# ADC.net
KiCad netlist of a schematic drawn in Altium Designer
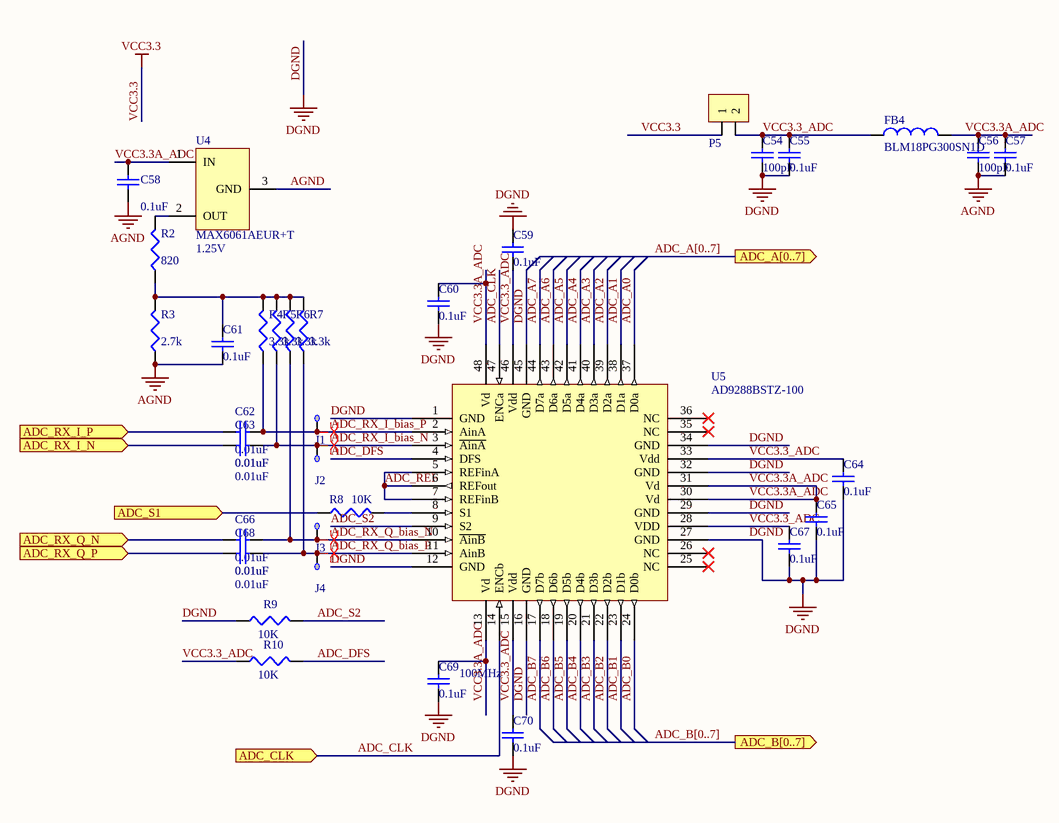
[diagram p0: ADC.SchDoc]

(export (version "E")
  (design (tool "Eeschema 10.0.6"))
  (components
    (comp (ref "C54")
      (value "100pF")
      (footprint "0402")
      (description "Capacitor (Semiconductor SIM Model)")
      (fields (field (name "PUBLISHER") "Altium Limited"))
      (libsource (lib "Miscellaneous Devices") (part "Cap Semi"))
    )
    (comp (ref "C55")
      (value "0.1uF")
      (footprint "0402")
      (description "Capacitor (Semiconductor SIM Model)")
      (fields (field (name "PUBLISHER") "Altium Limited"))
      (libsource (lib "Miscellaneous Devices") (part "Cap Semi"))
    )
    (comp (ref "C56")
      (value "100pF")
      (footprint "0402")
      (description "Capacitor (Semiconductor SIM Model)")
      (fields (field (name "PUBLISHER") "Altium Limited"))
      (libsource (lib "Miscellaneous Devices") (part "Cap Semi"))
    )
    (comp (ref "C57")
      (value "0.1uF")
      (footprint "0402")
      (description "Capacitor (Semiconductor SIM Model)")
      (fields (field (name "PUBLISHER") "Altium Limited"))
      (libsource (lib "Miscellaneous Devices") (part "Cap Semi"))
    )
    (comp (ref "C58")
      (value "0.1uF")
      (footprint "0402")
      (description "Capacitor (Semiconductor SIM Model)")
      (fields (field (name "PUBLISHER") "Altium Limited"))
      (libsource (lib "Miscellaneous Devices") (part "Cap Semi"))
    )
    (comp (ref "C59")
      (value "0.1uF")
      (footprint "0402")
      (description "Capacitor (Semiconductor SIM Model)")
      (fields (field (name "PUBLISHER") "Altium Limited"))
      (libsource (lib "Miscellaneous Devices") (part "Cap Semi"))
    )
    (comp (ref "C60")
      (value "0.1uF")
      (footprint "0402")
      (description "Capacitor (Semiconductor SIM Model)")
      (fields (field (name "PUBLISHER") "Altium Limited"))
      (libsource (lib "Miscellaneous Devices") (part "Cap Semi"))
    )
    (comp (ref "C61")
      (value "0.1uF")
      (footprint "0402")
      (description "Capacitor (Semiconductor SIM Model)")
      (fields (field (name "PUBLISHER") "Altium Limited"))
      (libsource (lib "Miscellaneous Devices") (part "Cap Semi"))
    )
    (comp (ref "C62")
      (value "0.01uF")
      (footprint "0402")
      (description "Capacitor (Semiconductor SIM Model)")
      (fields (field (name "ALTIUM_VALUE") "0.01uF") (field (name "PUBLISHER") "Altium Limited"))
      (libsource (lib "Miscellaneous Devices") (part "Cap Semi"))
    )
    (comp (ref "C63")
      (value "0.01uF")
      (footprint "0402")
      (description "Capacitor (Semiconductor SIM Model)")
      (fields (field (name "ALTIUM_VALUE") "0.01uF") (field (name "PUBLISHER") "Altium Limited"))
      (libsource (lib "Miscellaneous Devices") (part "Cap Semi"))
    )
    (comp (ref "C64")
      (value "0.1uF")
      (footprint "0402")
      (description "Capacitor (Semiconductor SIM Model)")
      (fields (field (name "PUBLISHER") "Altium Limited"))
      (libsource (lib "Miscellaneous Devices") (part "Cap Semi"))
    )
    (comp (ref "C65")
      (value "0.1uF")
      (footprint "0402")
      (description "Capacitor (Semiconductor SIM Model)")
      (fields (field (name "PUBLISHER") "Altium Limited"))
      (libsource (lib "Miscellaneous Devices") (part "Cap Semi"))
    )
    (comp (ref "C66")
      (value "0.01uF")
      (footprint "0402")
      (description "Capacitor (Semiconductor SIM Model)")
      (fields (field (name "ALTIUM_VALUE") "0.01uF") (field (name "PUBLISHER") "Altium Limited"))
      (libsource (lib "Miscellaneous Devices") (part "Cap Semi"))
    )
    (comp (ref "C67")
      (value "0.1uF")
      (footprint "0402")
      (description "Capacitor (Semiconductor SIM Model)")
      (fields (field (name "PUBLISHER") "Altium Limited"))
      (libsource (lib "Miscellaneous Devices") (part "Cap Semi"))
    )
    (comp (ref "C68")
      (value "0.01uF")
      (footprint "0402")
      (description "Capacitor (Semiconductor SIM Model)")
      (fields (field (name "ALTIUM_VALUE") "0.01uF") (field (name "PUBLISHER") "Altium Limited"))
      (libsource (lib "Miscellaneous Devices") (part "Cap Semi"))
    )
    (comp (ref "C69")
      (value "0.1uF")
      (footprint "0402")
      (description "Capacitor (Semiconductor SIM Model)")
      (fields (field (name "PUBLISHER") "Altium Limited"))
      (libsource (lib "Miscellaneous Devices") (part "Cap Semi"))
    )
    (comp (ref "C70")
      (value "0.1uF")
      (footprint "0402")
      (description "Capacitor (Semiconductor SIM Model)")
      (fields (field (name "PUBLISHER") "Altium Limited"))
      (libsource (lib "Miscellaneous Devices") (part "Cap Semi"))
    )
    (comp (ref "FB4")
      (value "BLM18PG300SN1D")
      (footprint "1608[0603]")
      (description "FERRITE CHIP 30 OHM 1000MA 0603")
      (libsource (lib "SDR") (part "Ferrite Bead"))
    )
    (comp (ref "J1")
      (value "5004")
      (footprint "TestPoint")
      (description "TEST POINT PC MINI .040\"D YELLOW")
      (libsource (lib "SDR") (part "TestPoint"))
    )
    (comp (ref "J2")
      (value "5004")
      (footprint "TestPoint")
      (description "TEST POINT PC MINI .040\"D YELLOW")
      (libsource (lib "SDR") (part "TestPoint"))
    )
    (comp (ref "J3")
      (value "5004")
      (footprint "TestPoint")
      (description "TEST POINT PC MINI .040\"D YELLOW")
      (libsource (lib "SDR") (part "TestPoint"))
    )
    (comp (ref "J4")
      (value "5004")
      (footprint "TestPoint")
      (description "TEST POINT PC MINI .040\"D YELLOW")
      (libsource (lib "SDR") (part "TestPoint"))
    )
    (comp (ref "P5")
      (value "1 x 2 header")
      (footprint "1x2 header")
      (description "100 mils standard header")
      (libsource (lib "SDR") (part "1 x 2 header"))
    )
    (comp (ref "R2")
      (value "820")
      (footprint "0402")
      (description "Resistor")
      (fields (field (name "PUBLISHER") "Altium Limited"))
      (libsource (lib "Miscellaneous Devices") (part "Res3"))
    )
    (comp (ref "R3")
      (value "2.7k")
      (footprint "0402")
      (description "Resistor")
      (fields (field (name "Comment") "2.7K") (field (name "PUBLISHER") "Altium Limited"))
      (libsource (lib "Miscellaneous Devices") (part "Res3"))
    )
    (comp (ref "R4")
      (value "3.3k")
      (footprint "0402")
      (description "Resistor")
      (fields (field (name "Comment") "3.3K") (field (name "PUBLISHER") "Altium Limited"))
      (libsource (lib "Miscellaneous Devices") (part "Res3"))
    )
    (comp (ref "R5")
      (value "3.3k")
      (footprint "0402")
      (description "Resistor")
      (fields (field (name "Comment") "3.3K") (field (name "PUBLISHER") "Altium Limited"))
      (libsource (lib "Miscellaneous Devices") (part "Res3"))
    )
    (comp (ref "R6")
      (value "3.3k")
      (footprint "0402")
      (description "Resistor")
      (fields (field (name "Comment") "3.3K") (field (name "PUBLISHER") "Altium Limited"))
      (libsource (lib "Miscellaneous Devices") (part "Res3"))
    )
    (comp (ref "R7")
      (value "3.3k")
      (footprint "0402")
      (description "Resistor")
      (fields (field (name "Comment") "3.3K") (field (name "PUBLISHER") "Altium Limited"))
      (libsource (lib "Miscellaneous Devices") (part "Res3"))
    )
    (comp (ref "R8")
      (value "10K")
      (footprint "0402")
      (description "Resistor")
      (fields (field (name "PUBLISHER") "Altium Limited"))
      (libsource (lib "Miscellaneous Devices") (part "Res3"))
    )
    (comp (ref "R9")
      (value "10K")
      (footprint "0402")
      (description "Resistor")
      (fields (field (name "PUBLISHER") "Altium Limited"))
      (libsource (lib "Miscellaneous Devices") (part "Res3"))
    )
    (comp (ref "R10")
      (value "10K")
      (footprint "0402")
      (description "Resistor")
      (fields (field (name "PUBLISHER") "Altium Limited"))
      (libsource (lib "Miscellaneous Devices") (part "Res3"))
    )
    (comp (ref "U4")
      (value "MAX6061AEUR+T")
      (footprint "SOT23-3N")
      (description "IC REF VOLT LDO SOT23-3")
      (fields (field (name "ALTIUM_VALUE") "1.25V"))
      (libsource (lib "SDR") (part "MAX6061"))
    )
    (comp (ref "U5")
      (value "AD9288BSTZ-100")
      (footprint "TSQFP50P900X900X160-48N")
      (description "IC ADC 8BIT DUAL 100MSPS 48-LQFP")
      (fields (field (name "ALTIUM_VALUE") "100MHz"))
      (libsource (lib "SDR") (part "AD9288"))
    )
  )
  (nets
    (net (code "1") (name "/ADC_A0") (class "Default")
      (node (ref "U5") (pin "37") (pinfunction "D0a_37") (pintype "output"))
    )
    (net (code "2") (name "/ADC_A1") (class "Default")
      (node (ref "U5") (pin "38") (pinfunction "D1a_38") (pintype "output"))
    )
    (net (code "3") (name "/ADC_A2") (class "Default")
      (node (ref "U5") (pin "39") (pinfunction "D2a_39") (pintype "output"))
    )
    (net (code "4") (name "/ADC_A3") (class "Default")
      (node (ref "U5") (pin "40") (pinfunction "D3a_40") (pintype "output"))
    )
    (net (code "5") (name "/ADC_A4") (class "Default")
      (node (ref "U5") (pin "41") (pinfunction "D4a_41") (pintype "output"))
    )
    (net (code "6") (name "/ADC_A5") (class "Default")
      (node (ref "U5") (pin "42") (pinfunction "D5a_42") (pintype "output"))
    )
    (net (code "7") (name "/ADC_A6") (class "Default")
      (node (ref "U5") (pin "43") (pinfunction "D6a_43") (pintype "output"))
    )
    (net (code "8") (name "/ADC_A7") (class "Default")
      (node (ref "U5") (pin "44") (pinfunction "D7a_44") (pintype "output"))
    )
    (net (code "10") (name "/ADC_B0") (class "Default")
      (node (ref "U5") (pin "24") (pinfunction "D0b_24") (pintype "output"))
    )
    (net (code "11") (name "/ADC_B1") (class "Default")
      (node (ref "U5") (pin "23") (pinfunction "D1b_23") (pintype "output"))
    )
    (net (code "12") (name "/ADC_B2") (class "Default")
      (node (ref "U5") (pin "22") (pinfunction "D2b_22") (pintype "output"))
    )
    (net (code "13") (name "/ADC_B3") (class "Default")
      (node (ref "U5") (pin "21") (pinfunction "D3b_21") (pintype "output"))
    )
    (net (code "14") (name "/ADC_B4") (class "Default")
      (node (ref "U5") (pin "20") (pinfunction "D4b_20") (pintype "output"))
    )
    (net (code "15") (name "/ADC_B5") (class "Default")
      (node (ref "U5") (pin "19") (pinfunction "D5b_19") (pintype "output"))
    )
    (net (code "16") (name "/ADC_B6") (class "Default")
      (node (ref "U5") (pin "18") (pinfunction "D6b_18") (pintype "output"))
    )
    (net (code "17") (name "/ADC_B7") (class "Default")
      (node (ref "U5") (pin "17") (pinfunction "D7b_17") (pintype "output"))
    )
    (net (code "19") (name "/ADC_CLK") (class "Default")
      (node (ref "U5") (pin "14") (pinfunction "ENCb_14") (pintype "input"))
      (node (ref "U5") (pin "47") (pinfunction "ENCa_47") (pintype "input"))
    )
    (net (code "20") (name "/ADC_DFS") (class "Default")
      (node (ref "R10") (pin "2") (pinfunction "2_2") (pintype "passive"))
      (node (ref "U5") (pin "4") (pinfunction "DFS_4") (pintype "input"))
    )
    (net (code "21") (name "/ADC_REF") (class "Default")
      (node (ref "U5") (pin "5") (pinfunction "REFinA_5") (pintype "input"))
      (node (ref "U5") (pin "6") (pinfunction "REFout_6") (pintype "output"))
      (node (ref "U5") (pin "7") (pinfunction "REFinB_7") (pintype "input"))
    )
    (net (code "22") (name "/ADC_RX_I_N") (class "Default")
      (node (ref "C63") (pin "1") (pinfunction "1_1") (pintype "passive"))
    )
    (net (code "23") (name "/ADC_RX_I_P") (class "Default")
      (node (ref "C62") (pin "1") (pinfunction "1_1") (pintype "passive"))
    )
    (net (code "24") (name "/ADC_RX_I_bias_N") (class "Default")
      (node (ref "C63") (pin "2") (pinfunction "2_2") (pintype "passive"))
      (node (ref "J2") (pin "1") (pinfunction "TB_1") (pintype "passive"))
      (node (ref "R5") (pin "1") (pinfunction "1_1") (pintype "passive"))
      (node (ref "U5") (pin "3") (pinfunction "~{AinA}_3") (pintype "input"))
    )
    (net (code "25") (name "/ADC_RX_I_bias_P") (class "Default")
      (node (ref "C62") (pin "2") (pinfunction "2_2") (pintype "passive"))
      (node (ref "J1") (pin "1") (pinfunction "TB_1") (pintype "passive"))
      (node (ref "R4") (pin "1") (pinfunction "1_1") (pintype "passive"))
      (node (ref "U5") (pin "2") (pinfunction "AinA_2") (pintype "input"))
    )
    (net (code "26") (name "/ADC_RX_Q_N") (class "Default")
      (node (ref "C66") (pin "1") (pinfunction "1_1") (pintype "passive"))
    )
    (net (code "27") (name "/ADC_RX_Q_P") (class "Default")
      (node (ref "C68") (pin "1") (pinfunction "1_1") (pintype "passive"))
    )
    (net (code "28") (name "/ADC_RX_Q_bias_N") (class "Default")
      (node (ref "C66") (pin "2") (pinfunction "2_2") (pintype "passive"))
      (node (ref "J3") (pin "1") (pinfunction "TB_1") (pintype "passive"))
      (node (ref "R6") (pin "1") (pinfunction "1_1") (pintype "passive"))
      (node (ref "U5") (pin "10") (pinfunction "~{AinB}_10") (pintype "input"))
    )
    (net (code "29") (name "/ADC_RX_Q_bias_P") (class "Default")
      (node (ref "C68") (pin "2") (pinfunction "2_2") (pintype "passive"))
      (node (ref "J4") (pin "1") (pinfunction "TB_1") (pintype "passive"))
      (node (ref "R7") (pin "1") (pinfunction "1_1") (pintype "passive"))
      (node (ref "U5") (pin "11") (pinfunction "AinB_11") (pintype "input"))
    )
    (net (code "30") (name "/ADC_S1") (class "Default")
      (node (ref "R8") (pin "1") (pinfunction "1_1") (pintype "passive"))
    )
    (net (code "31") (name "/ADC_S2") (class "Default")
      (node (ref "R9") (pin "2") (pinfunction "2_2") (pintype "passive"))
      (node (ref "U5") (pin "9") (pinfunction "S2_9") (pintype "input"))
    )
    (net (code "32") (name "/VCC3.3A_ADC") (class "Default")
      (node (ref "C56") (pin "2") (pinfunction "2_2") (pintype "passive"))
      (node (ref "C57") (pin "2") (pinfunction "2_2") (pintype "passive"))
      (node (ref "C58") (pin "2") (pinfunction "2_2") (pintype "passive"))
      (node (ref "C60") (pin "2") (pinfunction "2_2") (pintype "passive"))
      (node (ref "C65") (pin "2") (pinfunction "2_2") (pintype "passive"))
      (node (ref "C69") (pin "2") (pinfunction "2_2") (pintype "passive"))
      (node (ref "FB4") (pin "2") (pinfunction "2_2") (pintype "passive"))
      (node (ref "U4") (pin "1") (pinfunction "IN_1") (pintype "passive"))
      (node (ref "U5") (pin "13") (pinfunction "Vd_13") (pintype "passive"))
      (node (ref "U5") (pin "30") (pinfunction "Vd_30") (pintype "power_in"))
      (node (ref "U5") (pin "31") (pinfunction "Vd_31") (pintype "power_in"))
      (node (ref "U5") (pin "48") (pinfunction "Vd_48") (pintype "power_in"))
    )
    (net (code "33") (name "/VCC3.3_ADC") (class "Default")
      (node (ref "C54") (pin "2") (pinfunction "2_2") (pintype "passive"))
      (node (ref "C55") (pin "2") (pinfunction "2_2") (pintype "passive"))
      (node (ref "C59") (pin "1") (pinfunction "1_1") (pintype "passive"))
      (node (ref "C64") (pin "2") (pinfunction "2_2") (pintype "passive"))
      (node (ref "C67") (pin "2") (pinfunction "2_2") (pintype "passive"))
      (node (ref "C70") (pin "2") (pinfunction "2_2") (pintype "passive"))
      (node (ref "FB4") (pin "1") (pinfunction "1_1") (pintype "passive"))
      (node (ref "P5") (pin "2") (pinfunction "2_2") (pintype "passive"))
      (node (ref "R10") (pin "1") (pinfunction "1_1") (pintype "passive"))
      (node (ref "U5") (pin "15") (pinfunction "Vdd_15") (pintype "passive"))
      (node (ref "U5") (pin "28") (pinfunction "VDD_28") (pintype "power_in"))
      (node (ref "U5") (pin "33") (pinfunction "Vdd_33") (pintype "power_in"))
      (node (ref "U5") (pin "46") (pinfunction "Vdd_46") (pintype "power_in"))
    )
    (net (code "34") (name "AGND") (class "Default")
      (node (ref "C56") (pin "1") (pinfunction "1_1") (pintype "passive"))
      (node (ref "C57") (pin "1") (pinfunction "1_1") (pintype "passive"))
      (node (ref "C58") (pin "1") (pinfunction "1_1") (pintype "passive"))
      (node (ref "C61") (pin "1") (pinfunction "1_1") (pintype "passive"))
      (node (ref "R3") (pin "1") (pinfunction "1_1") (pintype "passive"))
      (node (ref "U4") (pin "3") (pinfunction "GND_3") (pintype "power_in"))
    )
    (net (code "35") (name "DGND") (class "Default")
      (node (ref "C54") (pin "1") (pinfunction "1_1") (pintype "passive"))
      (node (ref "C55") (pin "1") (pinfunction "1_1") (pintype "passive"))
      (node (ref "C59") (pin "2") (pinfunction "2_2") (pintype "passive"))
      (node (ref "C60") (pin "1") (pinfunction "1_1") (pintype "passive"))
      (node (ref "C64") (pin "1") (pinfunction "1_1") (pintype "passive"))
      (node (ref "C65") (pin "1") (pinfunction "1_1") (pintype "passive"))
      (node (ref "C67") (pin "1") (pinfunction "1_1") (pintype "passive"))
      (node (ref "C69") (pin "1") (pinfunction "1_1") (pintype "passive"))
      (node (ref "C70") (pin "1") (pinfunction "1_1") (pintype "passive"))
      (node (ref "R9") (pin "1") (pinfunction "1_1") (pintype "passive"))
      (node (ref "U5") (pin "1") (pinfunction "GND_1") (pintype "power_in"))
      (node (ref "U5") (pin "12") (pinfunction "GND_12") (pintype "power_in"))
      (node (ref "U5") (pin "16") (pinfunction "GND_16") (pintype "passive"))
      (node (ref "U5") (pin "27") (pinfunction "GND_27") (pintype "passive"))
      (node (ref "U5") (pin "29") (pinfunction "GND_29") (pintype "power_in"))
      (node (ref "U5") (pin "32") (pinfunction "GND_32") (pintype "power_in"))
      (node (ref "U5") (pin "34") (pinfunction "GND_34") (pintype "power_in"))
      (node (ref "U5") (pin "45") (pinfunction "GND_45") (pintype "power_in"))
    )
    (net (code "36") (name "Net-(C61-Pad2)") (class "Default")
      (node (ref "C61") (pin "2") (pinfunction "2_2") (pintype "passive"))
      (node (ref "R2") (pin "1") (pinfunction "1_1") (pintype "passive"))
      (node (ref "R3") (pin "2") (pinfunction "2_2") (pintype "passive"))
      (node (ref "R4") (pin "2") (pinfunction "2_2") (pintype "passive"))
      (node (ref "R5") (pin "2") (pinfunction "2_2") (pintype "passive"))
      (node (ref "R6") (pin "2") (pinfunction "2_2") (pintype "passive"))
      (node (ref "R7") (pin "2") (pinfunction "2_2") (pintype "passive"))
    )
    (net (code "37") (name "Net-(U4-OUT)") (class "Default")
      (node (ref "R2") (pin "2") (pinfunction "2_2") (pintype "passive"))
      (node (ref "U4") (pin "2") (pinfunction "OUT_2") (pintype "passive"))
    )
    (net (code "38") (name "Net-(U5-S1)") (class "Default")
      (node (ref "R8") (pin "2") (pinfunction "2_2") (pintype "passive"))
      (node (ref "U5") (pin "8") (pinfunction "S1_8") (pintype "input"))
    )
    (net (code "39") (name "VCC3.3") (class "Default")
      (node (ref "P5") (pin "1") (pinfunction "1_1") (pintype "passive"))
    )
    (net (code "40") (name "unconnected-(U5-NC-Pad25)") (class "Default")
      (node (ref "U5") (pin "25") (pinfunction "NC_25") (pintype "passive+no_connect"))
    )
    (net (code "41") (name "unconnected-(U5-NC-Pad26)") (class "Default")
      (node (ref "U5") (pin "26") (pinfunction "NC_26") (pintype "passive+no_connect"))
    )
    (net (code "42") (name "unconnected-(U5-NC-Pad35)") (class "Default")
      (node (ref "U5") (pin "35") (pinfunction "NC_35") (pintype "passive+no_connect"))
    )
    (net (code "43") (name "unconnected-(U5-NC-Pad36)") (class "Default")
      (node (ref "U5") (pin "36") (pinfunction "NC_36") (pintype "passive+no_connect"))
    )
  )
)
